# camera_trigger_control_v1_0.net
KiCad netlist of a schematic drawn in EAGLE
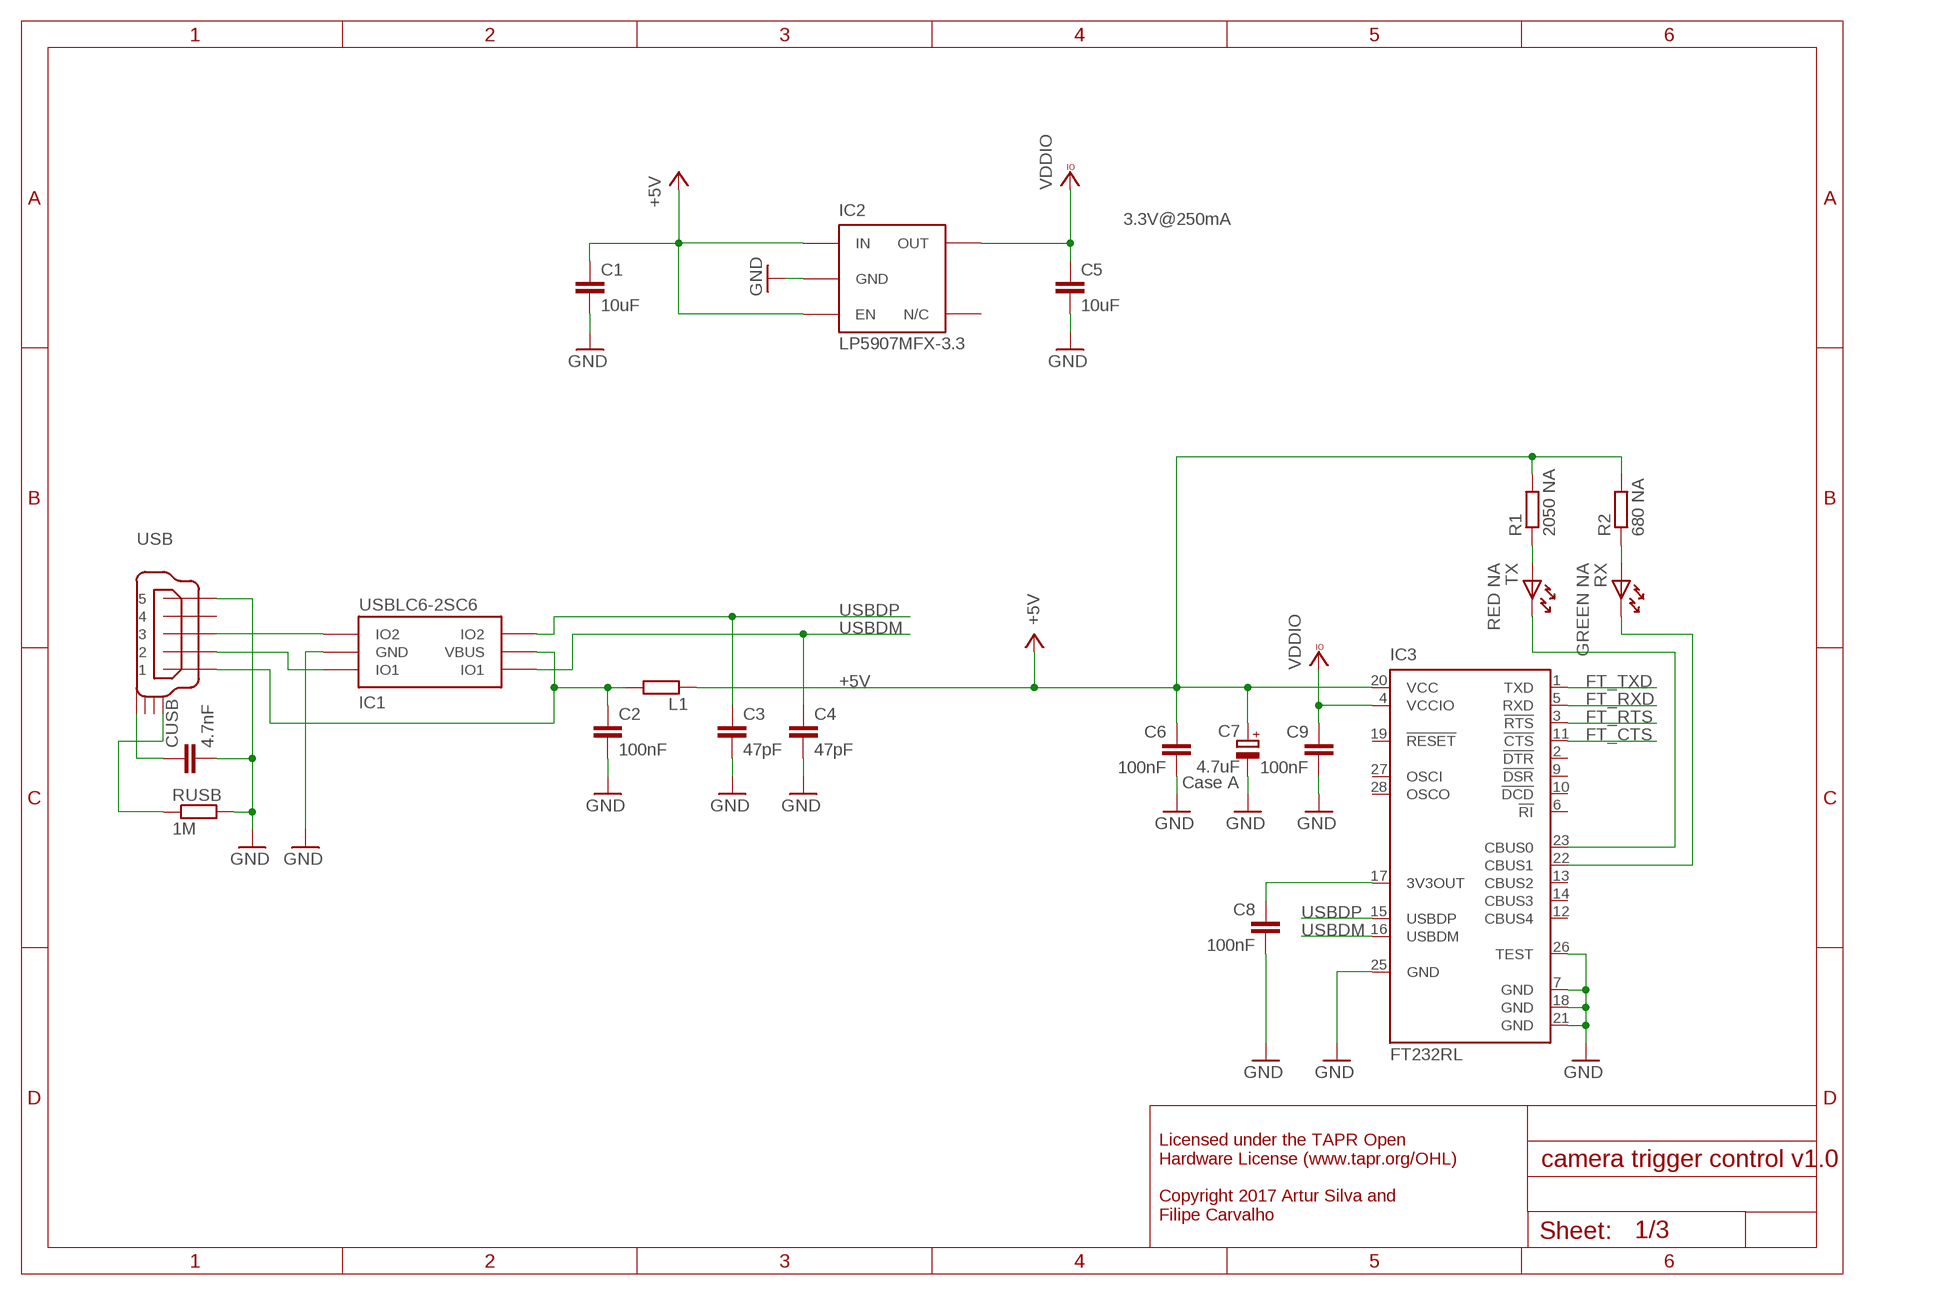
[diagram p0: schematic, sheet 1]
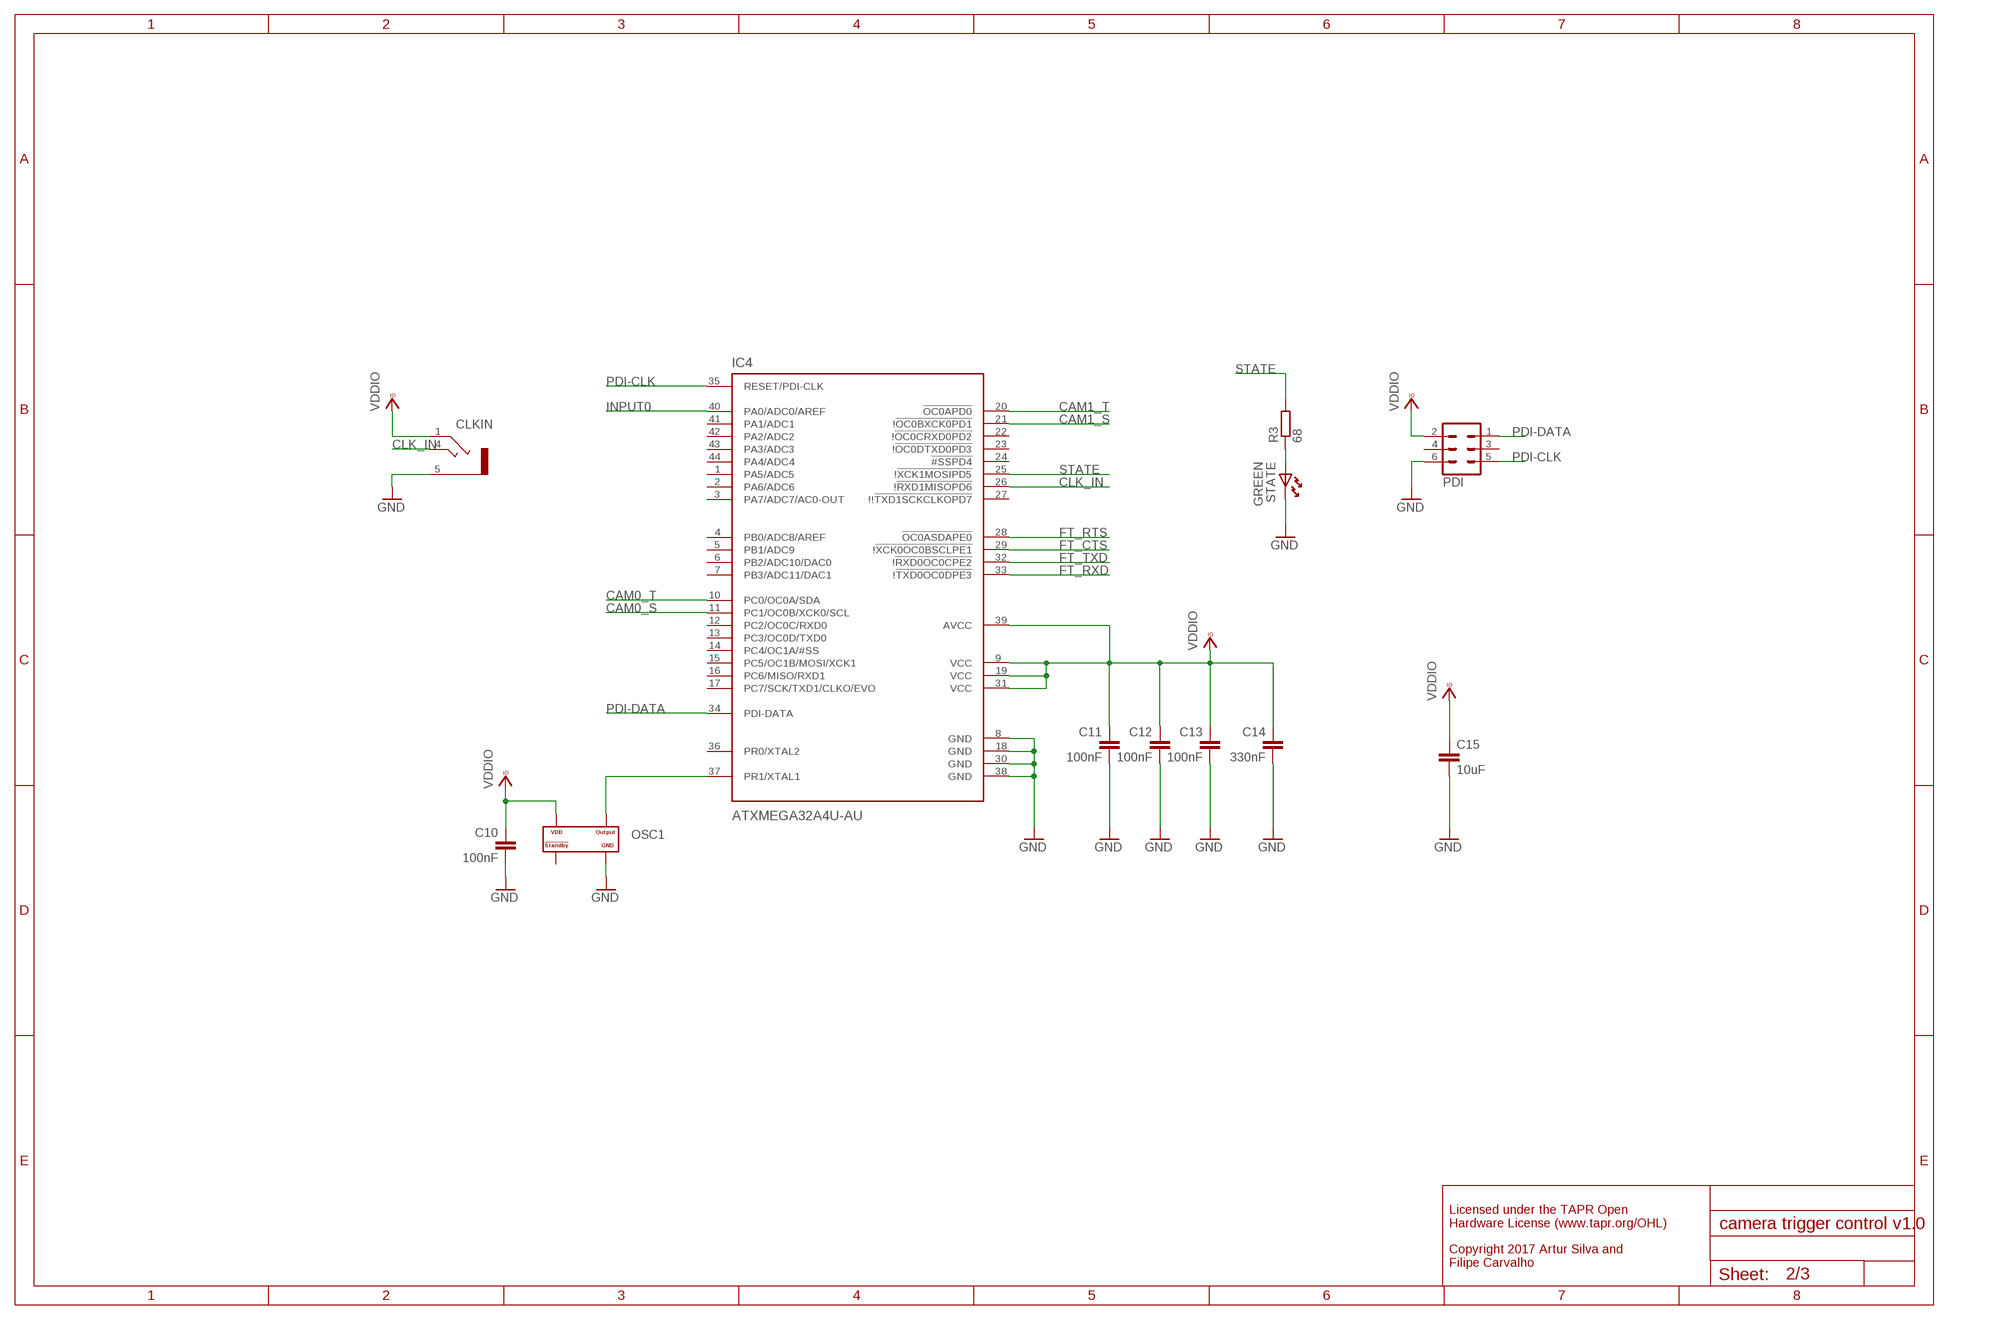
[diagram p1: schematic, sheet 2]
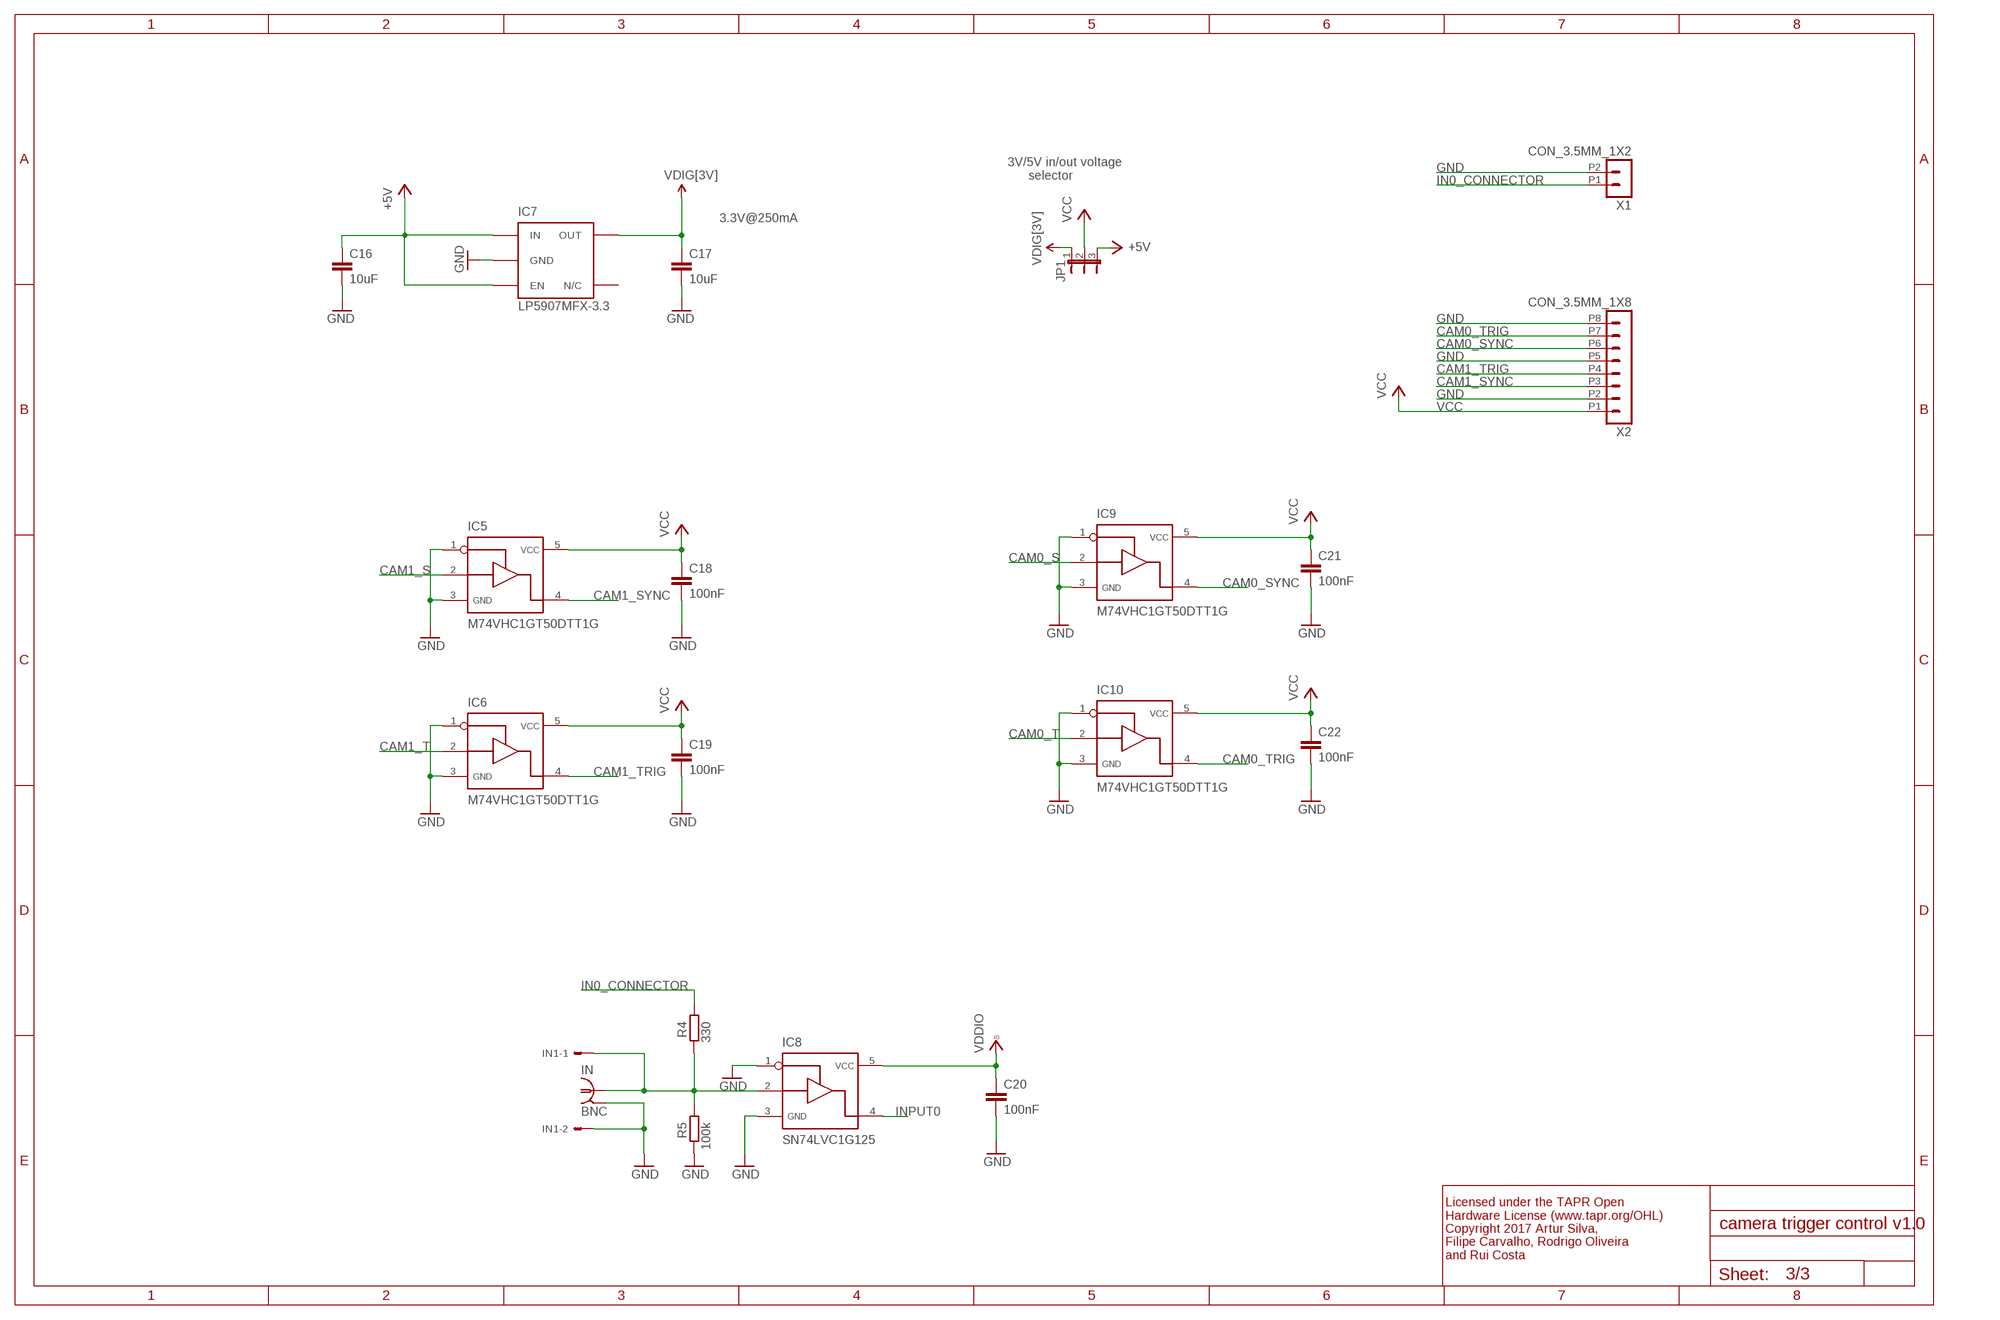
[diagram p2: schematic, sheet 3]

(export (version "E")
  (design (tool "Eeschema 10.0.6"))
  (components
    (comp (ref "C10")
      (value "100nF")
      (footprint "eagle-import:C0402")
      (libsource (lib "eagle-import") (part "C-EUC0402"))
    )
    (comp (ref "C11")
      (value "100nF")
      (footprint "eagle-import:C0402")
      (libsource (lib "eagle-import") (part "C-EUC0402"))
    )
    (comp (ref "C12")
      (value "100nF")
      (footprint "eagle-import:C0402")
      (libsource (lib "eagle-import") (part "C-EUC0402"))
    )
    (comp (ref "C13")
      (value "100nF")
      (footprint "eagle-import:C0402")
      (libsource (lib "eagle-import") (part "C-EUC0402"))
    )
    (comp (ref "C14")
      (value "330nF")
      (footprint "eagle-import:C0402")
      (libsource (lib "eagle-import") (part "C-EUC0402"))
    )
    (comp (ref "C15")
      (value "10uF")
      (footprint "eagle-import:C0603")
      (libsource (lib "eagle-import") (part "C-EUC0603"))
    )
    (comp (ref "CLKIN")
      (value "STEREO_JACK")
      (footprint "eagle-import:35RASMT2BHNTRX")
      (libsource (lib "eagle-import") (part "STEREO_JACK"))
    )
    (comp (ref "IC4")
      (value "ATXMEGA32A4U-AU")
      (footprint "eagle-import:QFP80P1200X1200X120-44N")
      (libsource (lib "eagle-import") (part "AT-XMEGA-XXA4-AU"))
    )
    (comp (ref "OSC1")
      (value "OSCILLATOR")
      (footprint "eagle-import:OSCILLATOR_3.2X2.5")
      (libsource (lib "eagle-import") (part "OSCILLATOR"))
    )
    (comp (ref "PDI")
      (value "MA03-2")
      (footprint "eagle-import:MA03-2")
      (libsource (lib "eagle-import") (part "MA03-2"))
    )
    (comp (ref "R3")
      (value "68")
      (footprint "eagle-import:R0402")
      (libsource (lib "eagle-import") (part "R-EU_R0402"))
    )
    (comp (ref "STATE")
      (value "GREEN")
      (footprint "eagle-import:LED_HAND")
      (libsource (lib "eagle-import") (part "LEDHAND"))
    )
    (comp (ref "C16")
      (value "10uF")
      (footprint "eagle-import:C0603")
      (libsource (lib "eagle-import") (part "C-EUC0603"))
    )
    (comp (ref "C17")
      (value "10uF")
      (footprint "eagle-import:C0603")
      (libsource (lib "eagle-import") (part "C-EUC0603"))
    )
    (comp (ref "C18")
      (value "100nF")
      (footprint "eagle-import:C0402")
      (libsource (lib "eagle-import") (part "C-EUC0402"))
    )
    (comp (ref "C19")
      (value "100nF")
      (footprint "eagle-import:C0402")
      (libsource (lib "eagle-import") (part "C-EUC0402"))
    )
    (comp (ref "C20")
      (value "100nF")
      (footprint "eagle-import:C0402")
      (libsource (lib "eagle-import") (part "C-EUC0402"))
    )
    (comp (ref "C21")
      (value "100nF")
      (footprint "eagle-import:C0402")
      (libsource (lib "eagle-import") (part "C-EUC0402"))
    )
    (comp (ref "C22")
      (value "100nF")
      (footprint "eagle-import:C0402")
      (libsource (lib "eagle-import") (part "C-EUC0402"))
    )
    (comp (ref "IC5")
      (value "M74VHC1GT50DTT1G")
      (footprint "eagle-import:SOT23-5")
      (libsource (lib "eagle-import") (part "SN74LVC1G125"))
    )
    (comp (ref "IC6")
      (value "M74VHC1GT50DTT1G")
      (footprint "eagle-import:SOT23-5")
      (libsource (lib "eagle-import") (part "SN74LVC1G125"))
    )
    (comp (ref "IC7")
      (value "LP5907MFX-3.3")
      (footprint "eagle-import:TSOT23-5")
      (libsource (lib "eagle-import") (part "TLV700XX"))
    )
    (comp (ref "IC8")
      (value "SN74LVC1G125")
      (footprint "eagle-import:SOT23-5")
      (libsource (lib "eagle-import") (part "SN74LVC1G125"))
    )
    (comp (ref "IC9")
      (value "M74VHC1GT50DTT1G")
      (footprint "eagle-import:SOT23-5")
      (libsource (lib "eagle-import") (part "SN74LVC1G125"))
    )
    (comp (ref "IC10")
      (value "M74VHC1GT50DTT1G")
      (footprint "eagle-import:SOT23-5")
      (libsource (lib "eagle-import") (part "SN74LVC1G125"))
    )
    (comp (ref "IN")
      (value "BNC")
      (footprint "eagle-import:BNC_RA")
      (libsource (lib "eagle-import") (part "BNC"))
    )
    (comp (ref "IN1")
      (value "22-05-7028-02")
      (footprint "eagle-import:7395-02")
      (libsource (lib "eagle-import") (part "22-?-0205-7028"))
    )
    (comp (ref "JP1")
      (value "JP2E")
      (footprint "eagle-import:JP2")
      (libsource (lib "eagle-import") (part "JP2E"))
    )
    (comp (ref "R4")
      (value "330")
      (footprint "eagle-import:R0402")
      (libsource (lib "eagle-import") (part "R-EU_R0402"))
    )
    (comp (ref "R5")
      (value "100k")
      (footprint "eagle-import:R0402")
      (libsource (lib "eagle-import") (part "R-EU_R0402"))
    )
    (comp (ref "X1")
      (value "CON_3.5MM_1X2")
      (footprint "eagle-import:CON_3.5MM_1X2")
      (libsource (lib "eagle-import") (part "CON_3.5MM_1X2"))
    )
    (comp (ref "X2")
      (value "CON_3.5MM_1X8")
      (footprint "eagle-import:CON_3.5MM_1X8")
      (libsource (lib "eagle-import") (part "CON_3.5MM_1X8"))
    )
    (comp (ref "C1")
      (value "10uF")
      (footprint "eagle-import:C0603")
      (libsource (lib "eagle-import") (part "C-EUC0603"))
    )
    (comp (ref "C2")
      (value "100nF")
      (footprint "eagle-import:C0402")
      (libsource (lib "eagle-import") (part "C-EUC0402"))
    )
    (comp (ref "C3")
      (value "47pF")
      (footprint "eagle-import:C0402")
      (libsource (lib "eagle-import") (part "C-EUC0402"))
    )
    (comp (ref "C4")
      (value "47pF")
      (footprint "eagle-import:C0402")
      (libsource (lib "eagle-import") (part "C-EUC0402"))
    )
    (comp (ref "C5")
      (value "10uF")
      (footprint "eagle-import:C0603")
      (libsource (lib "eagle-import") (part "C-EUC0603"))
    )
    (comp (ref "C6")
      (value "100nF")
      (footprint "eagle-import:C0402")
      (libsource (lib "eagle-import") (part "C-EUC0402"))
    )
    (comp (ref "C7")
      (value "4.7uF")
      (footprint "eagle-import:A_3216-18W")
      (libsource (lib "eagle-import") (part "CPOL-EUA/3216-18W"))
    )
    (comp (ref "C8")
      (value "100nF")
      (footprint "eagle-import:C0402")
      (libsource (lib "eagle-import") (part "C-EUC0402"))
    )
    (comp (ref "C9")
      (value "100nF")
      (footprint "eagle-import:C0402")
      (libsource (lib "eagle-import") (part "C-EUC0402"))
    )
    (comp (ref "CUSB")
      (value "4.7nF")
      (footprint "eagle-import:C0402")
      (libsource (lib "eagle-import") (part "C-EUC0402"))
    )
    (comp (ref "IC1")
      (value "USBLC6-2SC6")
      (footprint "eagle-import:SOT23-6L")
      (libsource (lib "eagle-import") (part "USBLC6-2"))
    )
    (comp (ref "IC2")
      (value "LP5907MFX-3.3")
      (footprint "eagle-import:TSOT23-5")
      (libsource (lib "eagle-import") (part "TLV700XX"))
    )
    (comp (ref "IC3")
      (value "FT232RL")
      (footprint "eagle-import:SSOP28")
      (libsource (lib "eagle-import") (part "FT232RL"))
    )
    (comp (ref "L1")
      (value "???")
      (footprint "eagle-import:R0805")
      (libsource (lib "eagle-import") (part "R-EU_R0805"))
    )
    (comp (ref "R1")
      (value "2050 NA")
      (footprint "eagle-import:R0402")
      (libsource (lib "eagle-import") (part "R-EU_R0402"))
    )
    (comp (ref "R2")
      (value "680 NA")
      (footprint "eagle-import:R0402")
      (libsource (lib "eagle-import") (part "R-EU_R0402"))
    )
    (comp (ref "RUSB")
      (value "1M")
      (footprint "eagle-import:R0402")
      (libsource (lib "eagle-import") (part "R-EU_R0402"))
    )
    (comp (ref "RX")
      (value "GREEN NA")
      (footprint "eagle-import:LED_HAND")
      (libsource (lib "eagle-import") (part "LEDHAND"))
    )
    (comp (ref "TX")
      (value "RED NA")
      (footprint "eagle-import:LED_HAND")
      (libsource (lib "eagle-import") (part "LEDHAND"))
    )
    (comp (ref "USB")
      (value "USB_MINI_B")
      (footprint "eagle-import:240-0002-1")
      (libsource (lib "eagle-import") (part "USB_MINI_B"))
    )
  )
  (nets
    (net (code "1") (name "+5V") (class "Default")
      (node (ref "C1") (pin "1") (pinfunction "1_1") (pintype "passive"))
      (node (ref "C16") (pin "1") (pinfunction "1_1") (pintype "passive"))
      (node (ref "C6") (pin "1") (pinfunction "1_1") (pintype "passive"))
      (node (ref "C7") (pin "+") (pinfunction "+_+") (pintype "passive"))
      (node (ref "IC2") (pin "1") (pinfunction "IN_1") (pintype "bidirectional"))
      (node (ref "IC2") (pin "3") (pinfunction "EN_3") (pintype "bidirectional"))
      (node (ref "IC3") (pin "20") (pinfunction "VCC_20") (pintype "power_in"))
      (node (ref "IC7") (pin "1") (pinfunction "IN_1") (pintype "bidirectional"))
      (node (ref "IC7") (pin "3") (pinfunction "EN_3") (pintype "bidirectional"))
      (node (ref "JP1") (pin "3") (pinfunction "3_3") (pintype "passive"))
      (node (ref "L1") (pin "1") (pinfunction "1_1") (pintype "passive"))
      (node (ref "R1") (pin "2") (pinfunction "2_2") (pintype "passive"))
      (node (ref "R2") (pin "2") (pinfunction "2_2") (pintype "passive"))
    )
    (net (code "2") (name "CAM0_S") (class "Default")
      (node (ref "IC4") (pin "11") (pinfunction "PC1/OC0B/XCK0/SCL_11") (pintype "bidirectional"))
      (node (ref "IC9") (pin "2") (pinfunction "P$2_2") (pintype "bidirectional"))
    )
    (net (code "3") (name "CAM0_SYNC") (class "Default")
      (node (ref "IC9") (pin "4") (pinfunction "P$4_4") (pintype "bidirectional"))
      (node (ref "X2") (pin "P6") (pinfunction "6_P6") (pintype "passive"))
    )
    (net (code "4") (name "CAM0_T") (class "Default")
      (node (ref "IC10") (pin "2") (pinfunction "P$2_2") (pintype "bidirectional"))
      (node (ref "IC4") (pin "10") (pinfunction "PC0/OC0A/SDA_10") (pintype "bidirectional"))
    )
    (net (code "5") (name "CAM0_TRIG") (class "Default")
      (node (ref "IC10") (pin "4") (pinfunction "P$4_4") (pintype "bidirectional"))
      (node (ref "X2") (pin "P7") (pinfunction "7_P7") (pintype "passive"))
    )
    (net (code "6") (name "CAM1_S") (class "Default")
      (node (ref "IC4") (pin "21") (pinfunction "~OC0BXCK0PD1_21") (pintype "bidirectional"))
      (node (ref "IC5") (pin "2") (pinfunction "P$2_2") (pintype "bidirectional"))
    )
    (net (code "7") (name "CAM1_SYNC") (class "Default")
      (node (ref "IC5") (pin "4") (pinfunction "P$4_4") (pintype "bidirectional"))
      (node (ref "X2") (pin "P3") (pinfunction "3_P3") (pintype "passive"))
    )
    (net (code "8") (name "CAM1_T") (class "Default")
      (node (ref "IC4") (pin "20") (pinfunction "~{OC0APD0}_20") (pintype "bidirectional"))
      (node (ref "IC6") (pin "2") (pinfunction "P$2_2") (pintype "bidirectional"))
    )
    (net (code "9") (name "CAM1_TRIG") (class "Default")
      (node (ref "IC6") (pin "4") (pinfunction "P$4_4") (pintype "bidirectional"))
      (node (ref "X2") (pin "P4") (pinfunction "4_P4") (pintype "passive"))
    )
    (net (code "10") (name "CLK_IN") (class "Default")
      (node (ref "CLKIN") (pin "4") (pinfunction "4_4") (pintype "passive"))
      (node (ref "IC4") (pin "26") (pinfunction "~RXD1MISOPD6_26") (pintype "bidirectional"))
    )
    (net (code "11") (name "FT_CTS") (class "Default")
      (node (ref "IC3") (pin "11") (pinfunction "~{CTS}_11") (pintype "input"))
      (node (ref "IC4") (pin "29") (pinfunction "~XCK0OC0BSCLPE1_29") (pintype "bidirectional"))
    )
    (net (code "12") (name "FT_RTS") (class "Default")
      (node (ref "IC3") (pin "3") (pinfunction "~{RTS}_3") (pintype "output"))
      (node (ref "IC4") (pin "28") (pinfunction "~{OC0ASDAPE0}_28") (pintype "bidirectional"))
    )
    (net (code "13") (name "FT_RXD") (class "Default")
      (node (ref "IC3") (pin "5") (pinfunction "RXD_5") (pintype "input"))
      (node (ref "IC4") (pin "33") (pinfunction "~TXD0OC0DPE3_33") (pintype "bidirectional"))
    )
    (net (code "14") (name "FT_TXD") (class "Default")
      (node (ref "IC3") (pin "1") (pinfunction "TXD_1") (pintype "output"))
      (node (ref "IC4") (pin "32") (pinfunction "~RXD0OC0CPE2_32") (pintype "bidirectional"))
    )
    (net (code "15") (name "GND") (class "Default")
      (node (ref "C1") (pin "2") (pinfunction "2_2") (pintype "passive"))
      (node (ref "C10") (pin "2") (pinfunction "2_2") (pintype "passive"))
      (node (ref "C11") (pin "2") (pinfunction "2_2") (pintype "passive"))
      (node (ref "C12") (pin "2") (pinfunction "2_2") (pintype "passive"))
      (node (ref "C13") (pin "2") (pinfunction "2_2") (pintype "passive"))
      (node (ref "C14") (pin "2") (pinfunction "2_2") (pintype "passive"))
      (node (ref "C15") (pin "2") (pinfunction "2_2") (pintype "passive"))
      (node (ref "C16") (pin "2") (pinfunction "2_2") (pintype "passive"))
      (node (ref "C17") (pin "2") (pinfunction "2_2") (pintype "passive"))
      (node (ref "C18") (pin "2") (pinfunction "2_2") (pintype "passive"))
      (node (ref "C19") (pin "2") (pinfunction "2_2") (pintype "passive"))
      (node (ref "C2") (pin "2") (pinfunction "2_2") (pintype "passive"))
      (node (ref "C20") (pin "2") (pinfunction "2_2") (pintype "passive"))
      (node (ref "C21") (pin "2") (pinfunction "2_2") (pintype "passive"))
      (node (ref "C22") (pin "2") (pinfunction "2_2") (pintype "passive"))
      (node (ref "C3") (pin "2") (pinfunction "2_2") (pintype "passive"))
      (node (ref "C4") (pin "2") (pinfunction "2_2") (pintype "passive"))
      (node (ref "C5") (pin "2") (pinfunction "2_2") (pintype "passive"))
      (node (ref "C6") (pin "2") (pinfunction "2_2") (pintype "passive"))
      (node (ref "C7") (pin "-") (pinfunction "-_-") (pintype "passive"))
      (node (ref "C8") (pin "2") (pinfunction "2_2") (pintype "passive"))
      (node (ref "C9") (pin "2") (pinfunction "2_2") (pintype "passive"))
      (node (ref "CLKIN") (pin "5") (pinfunction "5_5") (pintype "passive"))
      (node (ref "CUSB") (pin "2") (pinfunction "2_2") (pintype "passive"))
      (node (ref "IC1") (pin "P$2") (pinfunction "GND_P$2") (pintype "bidirectional"))
      (node (ref "IC10") (pin "1") (pinfunction "P$1_1") (pintype "bidirectional"))
      (node (ref "IC10") (pin "3") (pinfunction "P$3_3") (pintype "bidirectional"))
      (node (ref "IC2") (pin "2") (pinfunction "GND_2") (pintype "bidirectional"))
      (node (ref "IC3") (pin "18") (pinfunction "GND_18") (pintype "power_in"))
      (node (ref "IC3") (pin "21") (pinfunction "GND_21") (pintype "power_in"))
      (node (ref "IC3") (pin "25") (pinfunction "GND_25") (pintype "power_in"))
      (node (ref "IC3") (pin "26") (pinfunction "TEST_26") (pintype "input"))
      (node (ref "IC3") (pin "7") (pinfunction "GND_7") (pintype "power_in"))
      (node (ref "IC4") (pin "18") (pinfunction "GND_18") (pintype "power_in"))
      (node (ref "IC4") (pin "30") (pinfunction "GND_30") (pintype "power_in"))
      (node (ref "IC4") (pin "38") (pinfunction "GND_38") (pintype "power_in"))
      (node (ref "IC4") (pin "8") (pinfunction "GND_8") (pintype "power_in"))
      (node (ref "IC5") (pin "1") (pinfunction "P$1_1") (pintype "bidirectional"))
      (node (ref "IC5") (pin "3") (pinfunction "P$3_3") (pintype "bidirectional"))
      (node (ref "IC6") (pin "1") (pinfunction "P$1_1") (pintype "bidirectional"))
      (node (ref "IC6") (pin "3") (pinfunction "P$3_3") (pintype "bidirectional"))
      (node (ref "IC7") (pin "2") (pinfunction "GND_2") (pintype "bidirectional"))
      (node (ref "IC8") (pin "1") (pinfunction "P$1_1") (pintype "bidirectional"))
      (node (ref "IC8") (pin "3") (pinfunction "P$3_3") (pintype "bidirectional"))
      (node (ref "IC9") (pin "1") (pinfunction "P$1_1") (pintype "bidirectional"))
      (node (ref "IC9") (pin "3") (pinfunction "P$3_3") (pintype "bidirectional"))
      (node (ref "IN") (pin "2") (pinfunction "2_2") (pintype "passive"))
      (node (ref "IN1") (pin "2") (pinfunction "S_2") (pintype "passive"))
      (node (ref "OSC1") (pin "P$2") (pinfunction "GND_P$2") (pintype "passive"))
      (node (ref "PDI") (pin "6") (pinfunction "6_6") (pintype "passive"))
      (node (ref "R5") (pin "2") (pinfunction "2_2") (pintype "passive"))
      (node (ref "RUSB") (pin "2") (pinfunction "2_2") (pintype "passive"))
      (node (ref "STATE") (pin "K") (pinfunction "K_K") (pintype "bidirectional"))
      (node (ref "USB") (pin "P$5") (pinfunction "5_P$5") (pintype "bidirectional"))
      (node (ref "X1") (pin "P2") (pinfunction "2_P2") (pintype "passive"))
      (node (ref "X2") (pin "P2") (pinfunction "2_P2") (pintype "passive"))
      (node (ref "X2") (pin "P5") (pinfunction "5_P5") (pintype "passive"))
      (node (ref "X2") (pin "P8") (pinfunction "8_P8") (pintype "passive"))
    )
    (net (code "16") (name "IN0_CONNECTOR") (class "Default")
      (node (ref "R4") (pin "1") (pinfunction "1_1") (pintype "passive"))
      (node (ref "X1") (pin "P1") (pinfunction "1_P1") (pintype "passive"))
    )
    (net (code "17") (name "INPUT0") (class "Default")
      (node (ref "IC4") (pin "40") (pinfunction "PA0/ADC0/AREF_40") (pintype "bidirectional"))
      (node (ref "IC8") (pin "4") (pinfunction "P$4_4") (pintype "bidirectional"))
    )
    (net (code "18") (name "Net-(IC1-VBUS)") (class "Default")
      (node (ref "C2") (pin "1") (pinfunction "1_1") (pintype "passive"))
      (node (ref "IC1") (pin "P$5") (pinfunction "VBUS_P$5") (pintype "bidirectional"))
      (node (ref "L1") (pin "2") (pinfunction "2_2") (pintype "passive"))
      (node (ref "USB") (pin "P$1") (pinfunction "1_P$1") (pintype "bidirectional"))
    )
    (net (code "19") (name "Net-(IC3-3V3OUT)") (class "Default")
      (node (ref "C8") (pin "1") (pinfunction "1_1") (pintype "passive"))
      (node (ref "IC3") (pin "17") (pinfunction "3V3OUT_17") (pintype "output"))
    )
    (net (code "20") (name "Net-(IC3-CBUS0)") (class "Default")
      (node (ref "IC3") (pin "23") (pinfunction "CBUS0_23") (pintype "bidirectional"))
      (node (ref "TX") (pin "K") (pinfunction "K_K") (pintype "bidirectional"))
    )
    (net (code "21") (name "Net-(IC3-CBUS1)") (class "Default")
      (node (ref "IC3") (pin "22") (pinfunction "CBUS1_22") (pintype "bidirectional"))
      (node (ref "RX") (pin "K") (pinfunction "K_K") (pintype "bidirectional"))
    )
    (net (code "22") (name "Net-(IC4-PR1{slash}XTAL1)") (class "Default")
      (node (ref "IC4") (pin "37") (pinfunction "PR1/XTAL1_37") (pintype "bidirectional"))
      (node (ref "OSC1") (pin "P$3") (pinfunction "OUTPUT_P$3") (pintype "passive"))
    )
    (net (code "23") (name "Net-(IC8-P$2)") (class "Default")
      (node (ref "IC8") (pin "2") (pinfunction "P$2_2") (pintype "bidirectional"))
      (node (ref "IN") (pin "1") (pinfunction "1_1") (pintype "passive"))
      (node (ref "IN1") (pin "1") (pinfunction "S_1") (pintype "passive"))
      (node (ref "R4") (pin "2") (pinfunction "2_2") (pintype "passive"))
      (node (ref "R5") (pin "1") (pinfunction "1_1") (pintype "passive"))
    )
    (net (code "24") (name "Net-(R1-Pad1)") (class "Default")
      (node (ref "R1") (pin "1") (pinfunction "1_1") (pintype "passive"))
      (node (ref "TX") (pin "A") (pinfunction "A_A") (pintype "bidirectional"))
    )
    (net (code "25") (name "Net-(R2-Pad1)") (class "Default")
      (node (ref "R2") (pin "1") (pinfunction "1_1") (pintype "passive"))
      (node (ref "RX") (pin "A") (pinfunction "A_A") (pintype "bidirectional"))
    )
    (net (code "26") (name "Net-(R3-Pad1)") (class "Default")
      (node (ref "R3") (pin "1") (pinfunction "1_1") (pintype "passive"))
      (node (ref "STATE") (pin "A") (pinfunction "A_A") (pintype "bidirectional"))
    )
    (net (code "27") (name "Net-(USB-2)") (class "Default")
      (node (ref "IC1") (pin "P$1") (pinfunction "IO1_P$1") (pintype "bidirectional"))
      (node (ref "USB") (pin "P$2") (pinfunction "2_P$2") (pintype "bidirectional"))
    )
    (net (code "28") (name "Net-(USB-3)") (class "Default")
      (node (ref "IC1") (pin "P$3") (pinfunction "IO2_P$3") (pintype "bidirectional"))
      (node (ref "USB") (pin "P$3") (pinfunction "3_P$3") (pintype "bidirectional"))
    )
    (net (code "29") (name "Net-(USB-P$1)") (class "Default")
      (node (ref "RUSB") (pin "1") (pinfunction "1_1") (pintype "passive"))
      (node (ref "USB") (pin "SHIELD_1") (pinfunction "P$1_SHIELD_1") (pintype "bidirectional"))
    )
    (net (code "30") (name "Net-(USB-P$4)") (class "Default")
      (node (ref "CUSB") (pin "1") (pinfunction "1_1") (pintype "passive"))
      (node (ref "USB") (pin "SHIELD_4") (pinfunction "P$4_SHIELD_4") (pintype "bidirectional"))
    )
    (net (code "31") (name "PDI-CLK") (class "Default")
      (node (ref "IC4") (pin "35") (pinfunction "RESET/PDI-CLK_35") (pintype "input"))
      (node (ref "PDI") (pin "5") (pinfunction "5_5") (pintype "passive"))
    )
    (net (code "32") (name "PDI-DATA") (class "Default")
      (node (ref "IC4") (pin "34") (pinfunction "PDI-DATA_34") (pintype "bidirectional"))
      (node (ref "PDI") (pin "1") (pinfunction "1_1") (pintype "passive"))
    )
    (net (code "33") (name "STATE") (class "Default")
      (node (ref "IC4") (pin "25") (pinfunction "~XCK1MOSIPD5_25") (pintype "bidirectional"))
      (node (ref "R3") (pin "2") (pinfunction "2_2") (pintype "passive"))
    )
    (net (code "34") (name "USBDM") (class "Default")
      (node (ref "C4") (pin "1") (pinfunction "1_1") (pintype "passive"))
      (node (ref "IC1") (pin "P$6") (pinfunction "IO1_P$6") (pintype "bidirectional"))
      (node (ref "IC3") (pin "16") (pinfunction "USBDM_16") (pintype "bidirectional"))
    )
    (net (code "35") (name "USBDP") (class "Default")
      (node (ref "C3") (pin "1") (pinfunction "1_1") (pintype "passive"))
      (node (ref "IC1") (pin "P$4") (pinfunction "IO2_P$4") (pintype "bidirectional"))
      (node (ref "IC3") (pin "15") (pinfunction "USBDP_15") (pintype "bidirectional"))
    )
    (net (code "36") (name "VCC") (class "Default")
      (node (ref "C18") (pin "1") (pinfunction "1_1") (pintype "passive"))
      (node (ref "C19") (pin "1") (pinfunction "1_1") (pintype "passive"))
      (node (ref "C21") (pin "1") (pinfunction "1_1") (pintype "passive"))
      (node (ref "C22") (pin "1") (pinfunction "1_1") (pintype "passive"))
      (node (ref "IC10") (pin "5") (pinfunction "P$5_5") (pintype "bidirectional"))
      (node (ref "IC5") (pin "5") (pinfunction "P$5_5") (pintype "bidirectional"))
      (node (ref "IC6") (pin "5") (pinfunction "P$5_5") (pintype "bidirectional"))
      (node (ref "IC9") (pin "5") (pinfunction "P$5_5") (pintype "bidirectional"))
      (node (ref "JP1") (pin "2") (pinfunction "2_2") (pintype "passive"))
      (node (ref "X2") (pin "P1") (pinfunction "1_P1") (pintype "passive"))
    )
    (net (code "37") (name "VCCIO") (class "Default")
      (node (ref "C10") (pin "1") (pinfunction "1_1") (pintype "passive"))
      (node (ref "C11") (pin "1") (pinfunction "1_1") (pintype "passive"))
      (node (ref "C12") (pin "1") (pinfunction "1_1") (pintype "passive"))
      (node (ref "C13") (pin "1") (pinfunction "1_1") (pintype "passive"))
      (node (ref "C14") (pin "1") (pinfunction "1_1") (pintype "passive"))
      (node (ref "C15") (pin "1") (pinfunction "1_1") (pintype "passive"))
      (node (ref "C20") (pin "1") (pinfunction "1_1") (pintype "passive"))
      (node (ref "C5") (pin "1") (pinfunction "1_1") (pintype "passive"))
      (node (ref "C9") (pin "1") (pinfunction "1_1") (pintype "passive"))
      (node (ref "CLKIN") (pin "1") (pinfunction "1_1") (pintype "passive"))
      (node (ref "IC2") (pin "5") (pinfunction "OUT_5") (pintype "bidirectional"))
      (node (ref "IC3") (pin "4") (pinfunction "VCCIO_4") (pintype "power_in"))
      (node (ref "IC4") (pin "19") (pinfunction "VCC_19") (pintype "power_in"))
      (node (ref "IC4") (pin "31") (pinfunction "VCC_31") (pintype "power_in"))
      (node (ref "IC4") (pin "39") (pinfunction "AVCC_39") (pintype "power_in"))
      (node (ref "IC4") (pin "9") (pinfunction "VCC_9") (pintype "power_in"))
      (node (ref "IC8") (pin "5") (pinfunction "P$5_5") (pintype "bidirectional"))
      (node (ref "OSC1") (pin "P$4") (pinfunction "VDD_P$4") (pintype "passive"))
      (node (ref "PDI") (pin "2") (pinfunction "2_2") (pintype "passive"))
    )
    (net (code "38") (name "VDIG[3V]") (class "Default")
      (node (ref "C17") (pin "1") (pinfunction "1_1") (pintype "passive"))
      (node (ref "IC7") (pin "5") (pinfunction "OUT_5") (pintype "bidirectional"))
      (node (ref "JP1") (pin "1") (pinfunction "1_1") (pintype "passive"))
    )
    (net (code "39") (name "unconnected-(IC2-N{slash}C-Pad4)") (class "Default")
      (node (ref "IC2") (pin "4") (pinfunction "N/C_4") (pintype "bidirectional"))
    )
    (net (code "40") (name "unconnected-(IC3-CBUS2-Pad13)") (class "Default")
      (node (ref "IC3") (pin "13") (pinfunction "CBUS2_13") (pintype "bidirectional"))
    )
    (net (code "41") (name "unconnected-(IC3-CBUS3-Pad14)") (class "Default")
      (node (ref "IC3") (pin "14") (pinfunction "CBUS3_14") (pintype "bidirectional"))
    )
    (net (code "42") (name "unconnected-(IC3-CBUS4-Pad12)") (class "Default")
      (node (ref "IC3") (pin "12") (pinfunction "CBUS4_12") (pintype "bidirectional"))
    )
    (net (code "43") (name "unconnected-(IC3-OSCI-Pad27)") (class "Default")
      (node (ref "IC3") (pin "27") (pinfunction "OSCI_27") (pintype "input"))
    )
    (net (code "44") (name "unconnected-(IC3-OSCO-Pad28)") (class "Default")
      (node (ref "IC3") (pin "28") (pinfunction "OSCO_28") (pintype "output"))
    )
    (net (code "45") (name "unconnected-(IC3-~{DCD}-Pad10)") (class "Default")
      (node (ref "IC3") (pin "10") (pinfunction "~{DCD}_10") (pintype "input"))
    )
    (net (code "46") (name "unconnected-(IC3-~{DSR}-Pad9)") (class "Default")
      (node (ref "IC3") (pin "9") (pinfunction "~{DSR}_9") (pintype "input"))
    )
    (net (code "47") (name "unconnected-(IC3-~{DTR}-Pad2)") (class "Default")
      (node (ref "IC3") (pin "2") (pinfunction "~{DTR}_2") (pintype "output"))
    )
    (net (code "48") (name "unconnected-(IC3-~{RESET}-Pad19)") (class "Default")
      (node (ref "IC3") (pin "19") (pinfunction "~{RESET}_19") (pintype "input"))
    )
    (net (code "49") (name "unconnected-(IC3-~{RI}-Pad6)") (class "Default")
      (node (ref "IC3") (pin "6") (pinfunction "~{RI}_6") (pintype "input"))
    )
    (net (code "50") (name "unconnected-(IC4-PA1{slash}ADC1-Pad41)") (class "Default")
      (node (ref "IC4") (pin "41") (pinfunction "PA1/ADC1_41") (pintype "bidirectional"))
    )
    (net (code "51") (name "unconnected-(IC4-PA2{slash}ADC2-Pad42)") (class "Default")
      (node (ref "IC4") (pin "42") (pinfunction "PA2/ADC2_42") (pintype "bidirectional"))
    )
    (net (code "52") (name "unconnected-(IC4-PA3{slash}ADC3-Pad43)") (class "Default")
      (node (ref "IC4") (pin "43") (pinfunction "PA3/ADC3_43") (pintype "bidirectional"))
    )
    (net (code "53") (name "unconnected-(IC4-PA4{slash}ADC4-Pad44)") (class "Default")
      (node (ref "IC4") (pin "44") (pinfunction "PA4/ADC4_44") (pintype "bidirectional"))
    )
    (net (code "54") (name "unconnected-(IC4-PA5{slash}ADC5-Pad1)") (class "Default")
      (node (ref "IC4") (pin "1") (pinfunction "PA5/ADC5_1") (pintype "bidirectional"))
    )
    (net (code "55") (name "unconnected-(IC4-PA6{slash}ADC6-Pad2)") (class "Default")
      (node (ref "IC4") (pin "2") (pinfunction "PA6/ADC6_2") (pintype "bidirectional"))
    )
    (net (code "56") (name "unconnected-(IC4-PA7{slash}ADC7{slash}AC0-OUT-Pad3)") (class "Default")
      (node (ref "IC4") (pin "3") (pinfunction "PA7/ADC7/AC0-OUT_3") (pintype "bidirectional"))
    )
    (net (code "57") (name "unconnected-(IC4-PB0{slash}ADC8{slash}AREF-Pad4)") (class "Default")
      (node (ref "IC4") (pin "4") (pinfunction "PB0/ADC8/AREF_4") (pintype "bidirectional"))
    )
    (net (code "58") (name "unconnected-(IC4-PB1{slash}ADC9-Pad5)") (class "Default")
      (node (ref "IC4") (pin "5") (pinfunction "PB1/ADC9_5") (pintype "bidirectional"))
    )
    (net (code "59") (name "unconnected-(IC4-PB2{slash}ADC10{slash}DAC0-Pad6)") (class "Default")
      (node (ref "IC4") (pin "6") (pinfunction "PB2/ADC10/DAC0_6") (pintype "bidirectional"))
    )
    (net (code "60") (name "unconnected-(IC4-PB3{slash}ADC11{slash}DAC1-Pad7)") (class "Default")
      (node (ref "IC4") (pin "7") (pinfunction "PB3/ADC11/DAC1_7") (pintype "bidirectional"))
    )
    (net (code "61") (name "unconnected-(IC4-PC2{slash}OC0C{slash}RXD0-Pad12)") (class "Default")
      (node (ref "IC4") (pin "12") (pinfunction "PC2/OC0C/RXD0_12") (pintype "bidirectional"))
    )
    (net (code "62") (name "unconnected-(IC4-PC3{slash}OC0D{slash}TXD0-Pad13)") (class "Default")
      (node (ref "IC4") (pin "13") (pinfunction "PC3/OC0D/TXD0_13") (pintype "bidirectional"))
    )
    (net (code "63") (name "unconnected-(IC4-PC4{slash}OC1A{slash}#SS-Pad14)") (class "Default")
      (node (ref "IC4") (pin "14") (pinfunction "PC4/OC1A/#SS_14") (pintype "bidirectional"))
    )
    (net (code "64") (name "unconnected-(IC4-PC5{slash}OC1B{slash}MOSI{slash}XCK1-Pad15)") (class "Default")
      (node (ref "IC4") (pin "15") (pinfunction "PC5/OC1B/MOSI/XCK1_15") (pintype "bidirectional"))
    )
    (net (code "65") (name "unconnected-(IC4-PC6{slash}MISO{slash}RXD1-Pad16)") (class "Default")
      (node (ref "IC4") (pin "16") (pinfunction "PC6/MISO/RXD1_16") (pintype "bidirectional"))
    )
    (net (code "66") (name "unconnected-(IC4-PC7{slash}SCK{slash}TXD1{slash}CLKO{slash}EVO-Pad17)") (class "Default")
      (node (ref "IC4") (pin "17") (pinfunction "PC7/SCK/TXD1/CLKO/EVO_17") (pintype "bidirectional"))
    )
    (net (code "67") (name "unconnected-(IC4-PR0{slash}XTAL2-Pad36)") (class "Default")
      (node (ref "IC4") (pin "36") (pinfunction "PR0/XTAL2_36") (pintype "bidirectional"))
    )
    (net (code "68") (name "unconnected-(IC4-~OC0CRXD0PD2-Pad22)") (class "Default")
      (node (ref "IC4") (pin "22") (pinfunction "~OC0CRXD0PD2_22") (pintype "bidirectional"))
    )
    (net (code "69") (name "unconnected-(IC4-~OC0DTXD0PD3-Pad23)") (class "Default")
      (node (ref "IC4") (pin "23") (pinfunction "~OC0DTXD0PD3_23") (pintype "bidirectional"))
    )
    (net (code "70") (name "unconnected-(IC4-~{#SSPD4}-Pad24)") (class "Default")
      (node (ref "IC4") (pin "24") (pinfunction "~{#SSPD4}_24") (pintype "bidirectional"))
    )
    (net (code "71") (name "unconnected-(IC4-~~{TXD1SCKCLKOPD7}-Pad27)") (class "Default")
      (node (ref "IC4") (pin "27") (pinfunction "~~{TXD1SCKCLKOPD7}_27") (pintype "bidirectional"))
    )
    (net (code "72") (name "unconnected-(IC7-N{slash}C-Pad4)") (class "Default")
      (node (ref "IC7") (pin "4") (pinfunction "N/C_4") (pintype "bidirectional"))
    )
    (net (code "73") (name "unconnected-(OSC1-STANDBY#-PadP$1)") (class "Default")
      (node (ref "OSC1") (pin "P$1") (pinfunction "STANDBY#_P$1") (pintype "passive"))
    )
    (net (code "74") (name "unconnected-(PDI-Pad3)") (class "Default")
      (node (ref "PDI") (pin "3") (pinfunction "3_3") (pintype "passive"))
    )
    (net (code "75") (name "unconnected-(PDI-Pad4)") (class "Default")
      (node (ref "PDI") (pin "4") (pinfunction "4_4") (pintype "passive"))
    )
    (net (code "76") (name "unconnected-(USB-4-PadP$4)") (class "Default")
      (node (ref "USB") (pin "P$4") (pinfunction "4_P$4") (pintype "bidirectional"))
    )
    (net (code "77") (name "unconnected-(USB-P$2-PadSHIELD_2)") (class "Default")
      (node (ref "USB") (pin "SHIELD_2") (pinfunction "P$2_SHIELD_2") (pintype "bidirectional"))
    )
    (net (code "78") (name "unconnected-(USB-P$3-PadSHIELD_3)") (class "Default")
      (node (ref "USB") (pin "SHIELD_3") (pinfunction "P$3_SHIELD_3") (pintype "bidirectional"))
    )
  )
)
